# MC_Brekout-SPInew.net
KiCad netlist of a schematic drawn in EAGLE
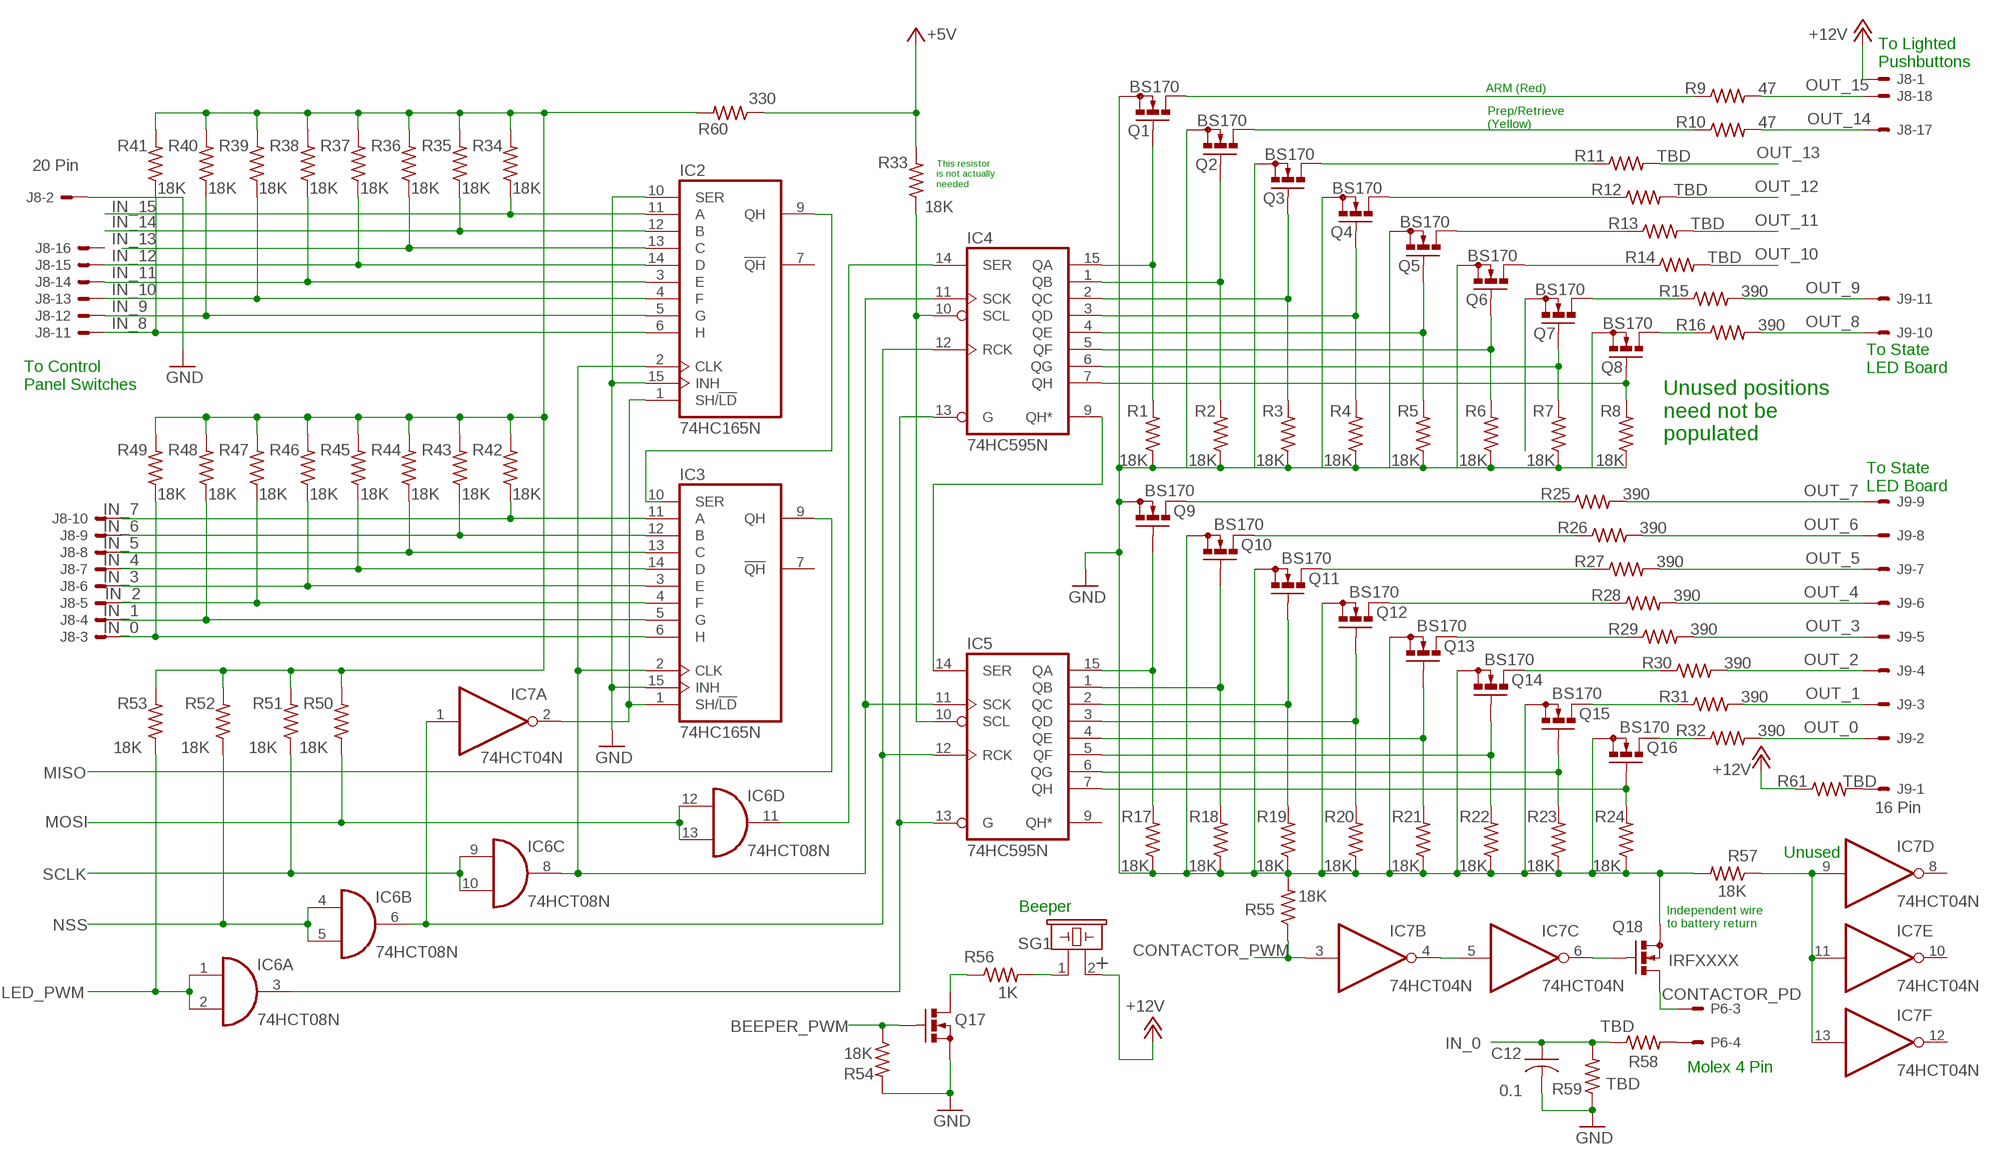
[diagram p0: schematic, sheet 1]

(export (version "E")
  (design (tool "Eeschema 10.0.6"))
  (components
    (comp (ref "C12")
      (value "0.1")
      (footprint "eagle-import:SMT0805")
      (libsource (lib "eagle-import") (part "SMT0805"))
    )
    (comp (ref "IC2")
      (value "74HC165N")
      (footprint "eagle-import:DIL16")
      (libsource (lib "eagle-import") (part "74165NHC"))
    )
    (comp (ref "IC3")
      (value "74HC165N")
      (footprint "eagle-import:DIL16")
      (libsource (lib "eagle-import") (part "74165NHC"))
    )
    (comp (ref "IC4")
      (value "74HC595N")
      (footprint "eagle-import:DIL16")
      (libsource (lib "eagle-import") (part "74595NHC"))
    )
    (comp (ref "IC5")
      (value "74HC595N")
      (footprint "eagle-import:DIL16")
      (libsource (lib "eagle-import") (part "74595NHC"))
    )
    (comp (ref "IC6")
      (value "74HCT08N")
      (footprint "eagle-import:DIL14")
      (libsource (lib "eagle-import") (part "7408NHCT"))
    )
    (comp (ref "IC7")
      (value "74HCT04N")
      (footprint "eagle-import:DIL14")
      (libsource (lib "eagle-import") (part "7404NHCT"))
    )
    (comp (ref "J8")
      (value "20 Pin")
      (footprint "eagle-import:70543-20")
      (libsource (lib "eagle-import") (part "C-GRID-20-70543"))
    )
    (comp (ref "J9")
      (value "16 Pin")
      (footprint "eagle-import:22-23-2121")
      (fields (field (name "MF") "MOLEX") (field (name "MPN") "22-23-2121"))
      (libsource (lib "eagle-import") (part "22-23-2121"))
    )
    (comp (ref "P6")
      (value "Molex 4 Pin")
      (footprint "eagle-import:22-23-2041")
      (fields (field (name "MF") "MOLEX") (field (name "MPN") "22-23-2041"))
      (libsource (lib "eagle-import") (part "22-23-2041"))
    )
    (comp (ref "Q1")
      (value "BS170")
      (footprint "eagle-import:SOT54E")
      (libsource (lib "eagle-import") (part "BS170"))
    )
    (comp (ref "Q2")
      (value "BS170")
      (footprint "eagle-import:SOT54E")
      (libsource (lib "eagle-import") (part "BS170"))
    )
    (comp (ref "Q3")
      (value "BS170")
      (footprint "eagle-import:SOT54E")
      (libsource (lib "eagle-import") (part "BS170"))
    )
    (comp (ref "Q4")
      (value "BS170")
      (footprint "eagle-import:SOT54E")
      (libsource (lib "eagle-import") (part "BS170"))
    )
    (comp (ref "Q5")
      (value "BS170")
      (footprint "eagle-import:SOT54E")
      (libsource (lib "eagle-import") (part "BS170"))
    )
    (comp (ref "Q6")
      (value "BS170")
      (footprint "eagle-import:SOT54E")
      (libsource (lib "eagle-import") (part "BS170"))
    )
    (comp (ref "Q7")
      (value "BS170")
      (footprint "eagle-import:SOT54E")
      (libsource (lib "eagle-import") (part "BS170"))
    )
    (comp (ref "Q8")
      (value "BS170")
      (footprint "eagle-import:SOT54E")
      (libsource (lib "eagle-import") (part "BS170"))
    )
    (comp (ref "Q9")
      (value "BS170")
      (footprint "eagle-import:SOT54E")
      (libsource (lib "eagle-import") (part "BS170"))
    )
    (comp (ref "Q10")
      (value "BS170")
      (footprint "eagle-import:SOT54E")
      (libsource (lib "eagle-import") (part "BS170"))
    )
    (comp (ref "Q11")
      (value "BS170")
      (footprint "eagle-import:SOT54E")
      (libsource (lib "eagle-import") (part "BS170"))
    )
    (comp (ref "Q12")
      (value "BS170")
      (footprint "eagle-import:SOT54E")
      (libsource (lib "eagle-import") (part "BS170"))
    )
    (comp (ref "Q13")
      (value "BS170")
      (footprint "eagle-import:SOT54E")
      (libsource (lib "eagle-import") (part "BS170"))
    )
    (comp (ref "Q14")
      (value "BS170")
      (footprint "eagle-import:SOT54E")
      (libsource (lib "eagle-import") (part "BS170"))
    )
    (comp (ref "Q15")
      (value "BS170")
      (footprint "eagle-import:SOT54E")
      (libsource (lib "eagle-import") (part "BS170"))
    )
    (comp (ref "Q16")
      (value "BS170")
      (footprint "eagle-import:SOT54E")
      (libsource (lib "eagle-import") (part "BS170"))
    )
    (comp (ref "Q17")
      (value "BS170")
      (footprint "eagle-import:SOT54E")
      (libsource (lib "eagle-import") (part "BS170"))
    )
    (comp (ref "Q18")
      (value "IRFXXXX")
      (footprint "eagle-import:SOT54E")
      (libsource (lib "eagle-import") (part "BS170"))
    )
    (comp (ref "R1")
      (value "18K")
      (footprint "eagle-import:V234_12")
      (libsource (lib "eagle-import") (part "R-US_V234/12"))
    )
    (comp (ref "R2")
      (value "18K")
      (footprint "eagle-import:V234_12")
      (libsource (lib "eagle-import") (part "R-US_V234/12"))
    )
    (comp (ref "R3")
      (value "18K")
      (footprint "eagle-import:V234_12")
      (libsource (lib "eagle-import") (part "R-US_V234/12"))
    )
    (comp (ref "R4")
      (value "18K")
      (footprint "eagle-import:V234_12")
      (libsource (lib "eagle-import") (part "R-US_V234/12"))
    )
    (comp (ref "R5")
      (value "18K")
      (footprint "eagle-import:V234_12")
      (libsource (lib "eagle-import") (part "R-US_V234/12"))
    )
    (comp (ref "R6")
      (value "18K")
      (footprint "eagle-import:V234_12")
      (libsource (lib "eagle-import") (part "R-US_V234/12"))
    )
    (comp (ref "R7")
      (value "18K")
      (footprint "eagle-import:V234_12")
      (libsource (lib "eagle-import") (part "R-US_V234/12"))
    )
    (comp (ref "R8")
      (value "18K")
      (footprint "eagle-import:V234_12")
      (libsource (lib "eagle-import") (part "R-US_V234/12"))
    )
    (comp (ref "R9")
      (value "47")
      (footprint "eagle-import:V234_12")
      (libsource (lib "eagle-import") (part "R-US_V234/12"))
    )
    (comp (ref "R10")
      (value "47")
      (footprint "eagle-import:V234_12")
      (libsource (lib "eagle-import") (part "R-US_V234/12"))
    )
    (comp (ref "R11")
      (value "TBD")
      (footprint "eagle-import:V234_12")
      (libsource (lib "eagle-import") (part "R-US_V234/12"))
    )
    (comp (ref "R12")
      (value "TBD")
      (footprint "eagle-import:V234_12")
      (libsource (lib "eagle-import") (part "R-US_V234/12"))
    )
    (comp (ref "R13")
      (value "TBD")
      (footprint "eagle-import:V234_12")
      (libsource (lib "eagle-import") (part "R-US_V234/12"))
    )
    (comp (ref "R14")
      (value "TBD")
      (footprint "eagle-import:V234_12")
      (libsource (lib "eagle-import") (part "R-US_V234/12"))
    )
    (comp (ref "R15")
      (value "390")
      (footprint "eagle-import:V234_12")
      (libsource (lib "eagle-import") (part "R-US_V234/12"))
    )
    (comp (ref "R16")
      (value "390")
      (footprint "eagle-import:V234_12")
      (libsource (lib "eagle-import") (part "R-US_V234/12"))
    )
    (comp (ref "R17")
      (value "18K")
      (footprint "eagle-import:V234_12")
      (libsource (lib "eagle-import") (part "R-US_V234/12"))
    )
    (comp (ref "R18")
      (value "18K")
      (footprint "eagle-import:V234_12")
      (libsource (lib "eagle-import") (part "R-US_V234/12"))
    )
    (comp (ref "R19")
      (value "18K")
      (footprint "eagle-import:V234_12")
      (libsource (lib "eagle-import") (part "R-US_V234/12"))
    )
    (comp (ref "R20")
      (value "18K")
      (footprint "eagle-import:V234_12")
      (libsource (lib "eagle-import") (part "R-US_V234/12"))
    )
    (comp (ref "R21")
      (value "18K")
      (footprint "eagle-import:V234_12")
      (libsource (lib "eagle-import") (part "R-US_V234/12"))
    )
    (comp (ref "R22")
      (value "18K")
      (footprint "eagle-import:V234_12")
      (libsource (lib "eagle-import") (part "R-US_V234/12"))
    )
    (comp (ref "R23")
      (value "18K")
      (footprint "eagle-import:V234_12")
      (libsource (lib "eagle-import") (part "R-US_V234/12"))
    )
    (comp (ref "R24")
      (value "18K")
      (footprint "eagle-import:V234_12")
      (libsource (lib "eagle-import") (part "R-US_V234/12"))
    )
    (comp (ref "R25")
      (value "390")
      (footprint "eagle-import:V234_12")
      (libsource (lib "eagle-import") (part "R-US_V234/12"))
    )
    (comp (ref "R26")
      (value "390")
      (footprint "eagle-import:V234_12")
      (libsource (lib "eagle-import") (part "R-US_V234/12"))
    )
    (comp (ref "R27")
      (value "390")
      (footprint "eagle-import:V234_12")
      (libsource (lib "eagle-import") (part "R-US_V234/12"))
    )
    (comp (ref "R28")
      (value "390")
      (footprint "eagle-import:V234_12")
      (libsource (lib "eagle-import") (part "R-US_V234/12"))
    )
    (comp (ref "R29")
      (value "390")
      (footprint "eagle-import:V234_12")
      (libsource (lib "eagle-import") (part "R-US_V234/12"))
    )
    (comp (ref "R30")
      (value "390")
      (footprint "eagle-import:V234_12")
      (libsource (lib "eagle-import") (part "R-US_V234/12"))
    )
    (comp (ref "R31")
      (value "390")
      (footprint "eagle-import:V234_12")
      (libsource (lib "eagle-import") (part "R-US_V234/12"))
    )
    (comp (ref "R32")
      (value "390")
      (footprint "eagle-import:V234_12")
      (libsource (lib "eagle-import") (part "R-US_V234/12"))
    )
    (comp (ref "R33")
      (value "18K")
      (footprint "eagle-import:V234_12")
      (libsource (lib "eagle-import") (part "R-US_V234/12"))
    )
    (comp (ref "R34")
      (value "18K")
      (footprint "eagle-import:V234_12")
      (libsource (lib "eagle-import") (part "R-US_V234/12"))
    )
    (comp (ref "R35")
      (value "18K")
      (footprint "eagle-import:V234_12")
      (libsource (lib "eagle-import") (part "R-US_V234/12"))
    )
    (comp (ref "R36")
      (value "18K")
      (footprint "eagle-import:V234_12")
      (libsource (lib "eagle-import") (part "R-US_V234/12"))
    )
    (comp (ref "R37")
      (value "18K")
      (footprint "eagle-import:V234_12")
      (libsource (lib "eagle-import") (part "R-US_V234/12"))
    )
    (comp (ref "R38")
      (value "18K")
      (footprint "eagle-import:V234_12")
      (libsource (lib "eagle-import") (part "R-US_V234/12"))
    )
    (comp (ref "R39")
      (value "18K")
      (footprint "eagle-import:V234_12")
      (libsource (lib "eagle-import") (part "R-US_V234/12"))
    )
    (comp (ref "R40")
      (value "18K")
      (footprint "eagle-import:V234_12")
      (libsource (lib "eagle-import") (part "R-US_V234/12"))
    )
    (comp (ref "R41")
      (value "18K")
      (footprint "eagle-import:V234_12")
      (libsource (lib "eagle-import") (part "R-US_V234/12"))
    )
    (comp (ref "R42")
      (value "18K")
      (footprint "eagle-import:V234_12")
      (libsource (lib "eagle-import") (part "R-US_V234/12"))
    )
    (comp (ref "R43")
      (value "18K")
      (footprint "eagle-import:V234_12")
      (libsource (lib "eagle-import") (part "R-US_V234/12"))
    )
    (comp (ref "R44")
      (value "18K")
      (footprint "eagle-import:V234_12")
      (libsource (lib "eagle-import") (part "R-US_V234/12"))
    )
    (comp (ref "R45")
      (value "18K")
      (footprint "eagle-import:V234_12")
      (libsource (lib "eagle-import") (part "R-US_V234/12"))
    )
    (comp (ref "R46")
      (value "18K")
      (footprint "eagle-import:V234_12")
      (libsource (lib "eagle-import") (part "R-US_V234/12"))
    )
    (comp (ref "R47")
      (value "18K")
      (footprint "eagle-import:V234_12")
      (libsource (lib "eagle-import") (part "R-US_V234/12"))
    )
    (comp (ref "R48")
      (value "18K")
      (footprint "eagle-import:V234_12")
      (libsource (lib "eagle-import") (part "R-US_V234/12"))
    )
    (comp (ref "R49")
      (value "18K")
      (footprint "eagle-import:V234_12")
      (libsource (lib "eagle-import") (part "R-US_V234/12"))
    )
    (comp (ref "R50")
      (value "18K")
      (footprint "eagle-import:V234_12")
      (libsource (lib "eagle-import") (part "R-US_V234/12"))
    )
    (comp (ref "R51")
      (value "18K")
      (footprint "eagle-import:V234_12")
      (libsource (lib "eagle-import") (part "R-US_V234/12"))
    )
    (comp (ref "R52")
      (value "18K")
      (footprint "eagle-import:V234_12")
      (libsource (lib "eagle-import") (part "R-US_V234/12"))
    )
    (comp (ref "R53")
      (value "18K")
      (footprint "eagle-import:V234_12")
      (libsource (lib "eagle-import") (part "R-US_V234/12"))
    )
    (comp (ref "R54")
      (value "18K")
      (footprint "eagle-import:V234_12")
      (libsource (lib "eagle-import") (part "R-US_V234/12"))
    )
    (comp (ref "R55")
      (value "18K")
      (footprint "eagle-import:V234_12")
      (libsource (lib "eagle-import") (part "R-US_V234/12"))
    )
    (comp (ref "R56")
      (value "1K")
      (footprint "eagle-import:V234_12")
      (libsource (lib "eagle-import") (part "R-US_V234/12"))
    )
    (comp (ref "R57")
      (value "18K")
      (footprint "eagle-import:V234_12")
      (libsource (lib "eagle-import") (part "R-US_V234/12"))
    )
    (comp (ref "R58")
      (value "TBD")
      (footprint "eagle-import:V234_12")
      (libsource (lib "eagle-import") (part "R-US_V234/12"))
    )
    (comp (ref "R59")
      (value "TBD")
      (footprint "eagle-import:V234_12")
      (libsource (lib "eagle-import") (part "R-US_V234/12"))
    )
    (comp (ref "R60")
      (value "330")
      (footprint "eagle-import:V234_12")
      (libsource (lib "eagle-import") (part "R-US_V234/12"))
    )
    (comp (ref "R61")
      (value "TBD")
      (footprint "eagle-import:V234_12")
      (libsource (lib "eagle-import") (part "R-US_V234/12"))
    )
    (comp (ref "SG1")
      (value "EFBAA40D101")
      (footprint "eagle-import:EFBAA40D101")
      (libsource (lib "eagle-import") (part "EFB?AA40D101"))
    )
  )
  (nets
    (net (code "1") (name "+5V") (class "Default")
      (node (ref "R33") (pin "2") (pinfunction "2_2") (pintype "passive"))
      (node (ref "R60") (pin "1") (pinfunction "1_1") (pintype "passive"))
    )
    (net (code "2") (name "+12V") (class "Default")
      (node (ref "J8") (pin "1") (pinfunction "S_1") (pintype "passive"))
      (node (ref "R61") (pin "1") (pinfunction "1_1") (pintype "passive"))
      (node (ref "SG1") (pin "2") (pinfunction "2_2") (pintype "passive"))
    )
    (net (code "3") (name "/BEEPER_PWM") (class "Default")
      (node (ref "Q17") (pin "G") (pinfunction "G_G") (pintype "passive"))
      (node (ref "R54") (pin "1") (pinfunction "1_1") (pintype "passive"))
    )
    (net (code "4") (name "/CONTACTOR_PD") (class "Default")
      (node (ref "P6") (pin "3") (pinfunction "S_3") (pintype "passive"))
      (node (ref "Q18") (pin "D") (pinfunction "D_D") (pintype "passive"))
    )
    (net (code "5") (name "/CONTACTOR_PWM") (class "Default")
      (node (ref "IC7") (pin "3") (pinfunction "I_3") (pintype "input"))
      (node (ref "R55") (pin "1") (pinfunction "1_1") (pintype "passive"))
    )
    (net (code "6") (name "/IN_0") (class "Default")
      (node (ref "C12") (pin "P$1") (pinfunction "1_P$1") (pintype "passive"))
      (node (ref "IC3") (pin "6") (pinfunction "H_6") (pintype "input"))
      (node (ref "J8") (pin "3") (pinfunction "S_3") (pintype "passive"))
      (node (ref "R49") (pin "1") (pinfunction "1_1") (pintype "passive"))
      (node (ref "R58") (pin "1") (pinfunction "1_1") (pintype "passive"))
      (node (ref "R59") (pin "2") (pinfunction "2_2") (pintype "passive"))
    )
    (net (code "7") (name "/IN_1") (class "Default")
      (node (ref "IC3") (pin "5") (pinfunction "G_5") (pintype "input"))
      (node (ref "J8") (pin "4") (pinfunction "S_4") (pintype "passive"))
      (node (ref "R48") (pin "1") (pinfunction "1_1") (pintype "passive"))
    )
    (net (code "8") (name "/IN_2") (class "Default")
      (node (ref "IC3") (pin "4") (pinfunction "F_4") (pintype "input"))
      (node (ref "J8") (pin "5") (pinfunction "S_5") (pintype "passive"))
      (node (ref "R47") (pin "1") (pinfunction "1_1") (pintype "passive"))
    )
    (net (code "9") (name "/IN_3") (class "Default")
      (node (ref "IC3") (pin "3") (pinfunction "E_3") (pintype "input"))
      (node (ref "J8") (pin "6") (pinfunction "S_6") (pintype "passive"))
      (node (ref "R46") (pin "1") (pinfunction "1_1") (pintype "passive"))
    )
    (net (code "10") (name "/IN_4") (class "Default")
      (node (ref "IC3") (pin "14") (pinfunction "D_14") (pintype "input"))
      (node (ref "J8") (pin "7") (pinfunction "S_7") (pintype "passive"))
      (node (ref "R45") (pin "1") (pinfunction "1_1") (pintype "passive"))
    )
    (net (code "11") (name "/IN_5") (class "Default")
      (node (ref "IC3") (pin "13") (pinfunction "C_13") (pintype "input"))
      (node (ref "J8") (pin "8") (pinfunction "S_8") (pintype "passive"))
      (node (ref "R44") (pin "1") (pinfunction "1_1") (pintype "passive"))
    )
    (net (code "12") (name "/IN_6") (class "Default")
      (node (ref "IC3") (pin "12") (pinfunction "B_12") (pintype "input"))
      (node (ref "J8") (pin "9") (pinfunction "S_9") (pintype "passive"))
      (node (ref "R43") (pin "1") (pinfunction "1_1") (pintype "passive"))
    )
    (net (code "13") (name "/IN_7") (class "Default")
      (node (ref "IC3") (pin "11") (pinfunction "A_11") (pintype "input"))
      (node (ref "J8") (pin "10") (pinfunction "S_10") (pintype "passive"))
      (node (ref "R42") (pin "1") (pinfunction "1_1") (pintype "passive"))
    )
    (net (code "14") (name "/IN_8") (class "Default")
      (node (ref "IC2") (pin "6") (pinfunction "H_6") (pintype "input"))
      (node (ref "J8") (pin "11") (pinfunction "S_11") (pintype "passive"))
      (node (ref "R41") (pin "1") (pinfunction "1_1") (pintype "passive"))
    )
    (net (code "15") (name "/IN_9") (class "Default")
      (node (ref "IC2") (pin "5") (pinfunction "G_5") (pintype "input"))
      (node (ref "J8") (pin "12") (pinfunction "S_12") (pintype "passive"))
      (node (ref "R40") (pin "1") (pinfunction "1_1") (pintype "passive"))
    )
    (net (code "16") (name "/IN_10") (class "Default")
      (node (ref "IC2") (pin "4") (pinfunction "F_4") (pintype "input"))
      (node (ref "J8") (pin "13") (pinfunction "S_13") (pintype "passive"))
      (node (ref "R39") (pin "1") (pinfunction "1_1") (pintype "passive"))
    )
    (net (code "17") (name "/IN_11") (class "Default")
      (node (ref "IC2") (pin "3") (pinfunction "E_3") (pintype "input"))
      (node (ref "J8") (pin "14") (pinfunction "S_14") (pintype "passive"))
      (node (ref "R38") (pin "1") (pinfunction "1_1") (pintype "passive"))
    )
    (net (code "18") (name "/IN_12") (class "Default")
      (node (ref "IC2") (pin "14") (pinfunction "D_14") (pintype "input"))
      (node (ref "J8") (pin "15") (pinfunction "S_15") (pintype "passive"))
      (node (ref "R37") (pin "1") (pinfunction "1_1") (pintype "passive"))
    )
    (net (code "19") (name "/IN_13") (class "Default")
      (node (ref "IC2") (pin "13") (pinfunction "C_13") (pintype "input"))
      (node (ref "R36") (pin "1") (pinfunction "1_1") (pintype "passive"))
    )
    (net (code "20") (name "/IN_14") (class "Default")
      (node (ref "IC2") (pin "12") (pinfunction "B_12") (pintype "input"))
      (node (ref "R35") (pin "1") (pinfunction "1_1") (pintype "passive"))
    )
    (net (code "21") (name "/IN_15") (class "Default")
      (node (ref "IC2") (pin "11") (pinfunction "A_11") (pintype "input"))
      (node (ref "R34") (pin "1") (pinfunction "1_1") (pintype "passive"))
    )
    (net (code "22") (name "/LED_PWM") (class "Default")
      (node (ref "IC6") (pin "1") (pinfunction "I0_1") (pintype "input"))
      (node (ref "IC6") (pin "2") (pinfunction "I1_2") (pintype "input"))
      (node (ref "R53") (pin "1") (pinfunction "1_1") (pintype "passive"))
    )
    (net (code "23") (name "/MISO") (class "Default")
      (node (ref "IC3") (pin "9") (pinfunction "QH_9") (pintype "output"))
    )
    (net (code "24") (name "/MOSI") (class "Default")
      (node (ref "IC6") (pin "12") (pinfunction "I0_12") (pintype "input"))
      (node (ref "IC6") (pin "13") (pinfunction "I1_13") (pintype "input"))
      (node (ref "R50") (pin "1") (pinfunction "1_1") (pintype "passive"))
    )
    (net (code "25") (name "/NSS") (class "Default")
      (node (ref "IC6") (pin "4") (pinfunction "I0_4") (pintype "input"))
      (node (ref "IC6") (pin "5") (pinfunction "I1_5") (pintype "input"))
      (node (ref "R52") (pin "1") (pinfunction "1_1") (pintype "passive"))
    )
    (net (code "26") (name "/OUT_0") (class "Default")
      (node (ref "J9") (pin "2") (pinfunction "S_2") (pintype "passive"))
      (node (ref "R32") (pin "2") (pinfunction "2_2") (pintype "passive"))
    )
    (net (code "27") (name "/OUT_1") (class "Default")
      (node (ref "J9") (pin "3") (pinfunction "S_3") (pintype "passive"))
      (node (ref "R31") (pin "2") (pinfunction "2_2") (pintype "passive"))
    )
    (net (code "28") (name "/OUT_2") (class "Default")
      (node (ref "J9") (pin "4") (pinfunction "S_4") (pintype "passive"))
      (node (ref "R30") (pin "2") (pinfunction "2_2") (pintype "passive"))
    )
    (net (code "29") (name "/OUT_3") (class "Default")
      (node (ref "J9") (pin "5") (pinfunction "S_5") (pintype "passive"))
      (node (ref "R29") (pin "2") (pinfunction "2_2") (pintype "passive"))
    )
    (net (code "30") (name "/OUT_4") (class "Default")
      (node (ref "J9") (pin "6") (pinfunction "S_6") (pintype "passive"))
      (node (ref "R28") (pin "2") (pinfunction "2_2") (pintype "passive"))
    )
    (net (code "31") (name "/OUT_5") (class "Default")
      (node (ref "J9") (pin "7") (pinfunction "S_7") (pintype "passive"))
      (node (ref "R27") (pin "2") (pinfunction "2_2") (pintype "passive"))
    )
    (net (code "32") (name "/OUT_6") (class "Default")
      (node (ref "J9") (pin "8") (pinfunction "S_8") (pintype "passive"))
      (node (ref "R26") (pin "2") (pinfunction "2_2") (pintype "passive"))
    )
    (net (code "33") (name "/OUT_7") (class "Default")
      (node (ref "J9") (pin "9") (pinfunction "S_9") (pintype "passive"))
      (node (ref "R25") (pin "2") (pinfunction "2_2") (pintype "passive"))
    )
    (net (code "34") (name "/OUT_8") (class "Default")
      (node (ref "J9") (pin "10") (pinfunction "S_10") (pintype "passive"))
      (node (ref "R16") (pin "2") (pinfunction "2_2") (pintype "passive"))
    )
    (net (code "35") (name "/OUT_9") (class "Default")
      (node (ref "J9") (pin "11") (pinfunction "S_11") (pintype "passive"))
      (node (ref "R15") (pin "2") (pinfunction "2_2") (pintype "passive"))
    )
    (net (code "36") (name "/OUT_10") (class "Default")
      (node (ref "R14") (pin "2") (pinfunction "2_2") (pintype "passive"))
    )
    (net (code "37") (name "/OUT_11") (class "Default")
      (node (ref "R13") (pin "2") (pinfunction "2_2") (pintype "passive"))
    )
    (net (code "38") (name "/OUT_12") (class "Default")
      (node (ref "R12") (pin "2") (pinfunction "2_2") (pintype "passive"))
    )
    (net (code "39") (name "/OUT_13") (class "Default")
      (node (ref "R11") (pin "2") (pinfunction "2_2") (pintype "passive"))
    )
    (net (code "40") (name "/OUT_14") (class "Default")
      (node (ref "J8") (pin "17") (pinfunction "S_17") (pintype "passive"))
      (node (ref "R10") (pin "2") (pinfunction "2_2") (pintype "passive"))
    )
    (net (code "41") (name "/OUT_15") (class "Default")
      (node (ref "J8") (pin "18") (pinfunction "S_18") (pintype "passive"))
      (node (ref "R9") (pin "2") (pinfunction "2_2") (pintype "passive"))
    )
    (net (code "42") (name "/SCLK") (class "Default")
      (node (ref "IC6") (pin "10") (pinfunction "I1_10") (pintype "input"))
      (node (ref "IC6") (pin "9") (pinfunction "I0_9") (pintype "input"))
      (node (ref "R51") (pin "1") (pinfunction "1_1") (pintype "passive"))
    )
    (net (code "43") (name "GND") (class "Default")
      (node (ref "C12") (pin "P$2") (pinfunction "2_P$2") (pintype "passive"))
      (node (ref "IC2") (pin "10") (pinfunction "SER_10") (pintype "input"))
      (node (ref "IC2") (pin "15") (pinfunction "INH_15") (pintype "input"))
      (node (ref "IC3") (pin "15") (pinfunction "INH_15") (pintype "input"))
      (node (ref "J8") (pin "2") (pinfunction "S_2") (pintype "passive"))
      (node (ref "Q1") (pin "S") (pinfunction "S_S") (pintype "passive"))
      (node (ref "Q10") (pin "S") (pinfunction "S_S") (pintype "passive"))
      (node (ref "Q11") (pin "S") (pinfunction "S_S") (pintype "passive"))
      (node (ref "Q12") (pin "S") (pinfunction "S_S") (pintype "passive"))
      (node (ref "Q13") (pin "S") (pinfunction "S_S") (pintype "passive"))
      (node (ref "Q14") (pin "S") (pinfunction "S_S") (pintype "passive"))
      (node (ref "Q15") (pin "S") (pinfunction "S_S") (pintype "passive"))
      (node (ref "Q16") (pin "S") (pinfunction "S_S") (pintype "passive"))
      (node (ref "Q17") (pin "S") (pinfunction "S_S") (pintype "passive"))
      (node (ref "Q18") (pin "S") (pinfunction "S_S") (pintype "passive"))
      (node (ref "Q9") (pin "S") (pinfunction "S_S") (pintype "passive"))
      (node (ref "R1") (pin "1") (pinfunction "1_1") (pintype "passive"))
      (node (ref "R17") (pin "1") (pinfunction "1_1") (pintype "passive"))
      (node (ref "R18") (pin "1") (pinfunction "1_1") (pintype "passive"))
      (node (ref "R19") (pin "1") (pinfunction "1_1") (pintype "passive"))
      (node (ref "R2") (pin "1") (pinfunction "1_1") (pintype "passive"))
      (node (ref "R20") (pin "1") (pinfunction "1_1") (pintype "passive"))
      (node (ref "R21") (pin "1") (pinfunction "1_1") (pintype "passive"))
      (node (ref "R22") (pin "1") (pinfunction "1_1") (pintype "passive"))
      (node (ref "R23") (pin "1") (pinfunction "1_1") (pintype "passive"))
      (node (ref "R24") (pin "1") (pinfunction "1_1") (pintype "passive"))
      (node (ref "R3") (pin "1") (pinfunction "1_1") (pintype "passive"))
      (node (ref "R4") (pin "1") (pinfunction "1_1") (pintype "passive"))
      (node (ref "R5") (pin "1") (pinfunction "1_1") (pintype "passive"))
      (node (ref "R54") (pin "2") (pinfunction "2_2") (pintype "passive"))
      (node (ref "R55") (pin "2") (pinfunction "2_2") (pintype "passive"))
      (node (ref "R57") (pin "2") (pinfunction "2_2") (pintype "passive"))
      (node (ref "R59") (pin "1") (pinfunction "1_1") (pintype "passive"))
      (node (ref "R6") (pin "1") (pinfunction "1_1") (pintype "passive"))
      (node (ref "R7") (pin "1") (pinfunction "1_1") (pintype "passive"))
      (node (ref "R8") (pin "1") (pinfunction "1_1") (pintype "passive"))
    )
    (net (code "44") (name "Net-(IC2A-CLK)") (class "Default")
      (node (ref "IC2") (pin "2") (pinfunction "CLK_2") (pintype "input"))
      (node (ref "IC3") (pin "2") (pinfunction "CLK_2") (pintype "input"))
      (node (ref "IC4") (pin "11") (pinfunction "SCK_11") (pintype "input"))
      (node (ref "IC5") (pin "11") (pinfunction "SCK_11") (pintype "input"))
      (node (ref "IC6") (pin "8") (pinfunction "O_8") (pintype "output"))
    )
    (net (code "45") (name "Net-(IC2A-QH)") (class "Default")
      (node (ref "IC2") (pin "9") (pinfunction "QH_9") (pintype "output"))
      (node (ref "IC3") (pin "10") (pinfunction "SER_10") (pintype "input"))
    )
    (net (code "46") (name "Net-(IC2A-SH{slash}~{LD})") (class "Default")
      (node (ref "IC2") (pin "1") (pinfunction "SH/~{LD}_1") (pintype "input"))
      (node (ref "IC3") (pin "1") (pinfunction "SH/~{LD}_1") (pintype "input"))
      (node (ref "IC7") (pin "2") (pinfunction "O_2") (pintype "output"))
    )
    (net (code "47") (name "Net-(IC4A-G)") (class "Default")
      (node (ref "IC4") (pin "13") (pinfunction "G_13") (pintype "input"))
      (node (ref "IC5") (pin "13") (pinfunction "G_13") (pintype "input"))
      (node (ref "IC6") (pin "3") (pinfunction "O_3") (pintype "output"))
    )
    (net (code "48") (name "Net-(IC4A-QA)") (class "Default")
      (node (ref "IC4") (pin "15") (pinfunction "QA_15") (pintype "tri_state"))
      (node (ref "Q1") (pin "G") (pinfunction "G_G") (pintype "passive"))
      (node (ref "R1") (pin "2") (pinfunction "2_2") (pintype "passive"))
    )
    (net (code "49") (name "Net-(IC4A-QB)") (class "Default")
      (node (ref "IC4") (pin "1") (pinfunction "QB_1") (pintype "tri_state"))
      (node (ref "Q2") (pin "G") (pinfunction "G_G") (pintype "passive"))
      (node (ref "R2") (pin "2") (pinfunction "2_2") (pintype "passive"))
    )
    (net (code "50") (name "Net-(IC4A-QC)") (class "Default")
      (node (ref "IC4") (pin "2") (pinfunction "QC_2") (pintype "tri_state"))
      (node (ref "Q3") (pin "G") (pinfunction "G_G") (pintype "passive"))
      (node (ref "R3") (pin "2") (pinfunction "2_2") (pintype "passive"))
    )
    (net (code "51") (name "Net-(IC4A-QD)") (class "Default")
      (node (ref "IC4") (pin "3") (pinfunction "QD_3") (pintype "tri_state"))
      (node (ref "Q4") (pin "G") (pinfunction "G_G") (pintype "passive"))
      (node (ref "R4") (pin "2") (pinfunction "2_2") (pintype "passive"))
    )
    (net (code "52") (name "Net-(IC4A-QE)") (class "Default")
      (node (ref "IC4") (pin "4") (pinfunction "QE_4") (pintype "tri_state"))
      (node (ref "Q5") (pin "G") (pinfunction "G_G") (pintype "passive"))
      (node (ref "R5") (pin "2") (pinfunction "2_2") (pintype "passive"))
    )
    (net (code "53") (name "Net-(IC4A-QF)") (class "Default")
      (node (ref "IC4") (pin "5") (pinfunction "QF_5") (pintype "tri_state"))
      (node (ref "Q6") (pin "G") (pinfunction "G_G") (pintype "passive"))
      (node (ref "R6") (pin "2") (pinfunction "2_2") (pintype "passive"))
    )
    (net (code "54") (name "Net-(IC4A-QG)") (class "Default")
      (node (ref "IC4") (pin "6") (pinfunction "QG_6") (pintype "tri_state"))
      (node (ref "Q7") (pin "G") (pinfunction "G_G") (pintype "passive"))
      (node (ref "R7") (pin "2") (pinfunction "2_2") (pintype "passive"))
    )
    (net (code "55") (name "Net-(IC4A-QH)") (class "Default")
      (node (ref "IC4") (pin "7") (pinfunction "QH_7") (pintype "tri_state"))
      (node (ref "Q8") (pin "G") (pinfunction "G_G") (pintype "passive"))
      (node (ref "R8") (pin "2") (pinfunction "2_2") (pintype "passive"))
    )
    (net (code "56") (name "Net-(IC4A-QH*)") (class "Default")
      (node (ref "IC4") (pin "9") (pinfunction "QH*_9") (pintype "tri_state"))
      (node (ref "IC5") (pin "14") (pinfunction "SER_14") (pintype "input"))
    )
    (net (code "57") (name "Net-(IC4A-RCK)") (class "Default")
      (node (ref "IC4") (pin "12") (pinfunction "RCK_12") (pintype "input"))
      (node (ref "IC5") (pin "12") (pinfunction "RCK_12") (pintype "input"))
      (node (ref "IC6") (pin "6") (pinfunction "O_6") (pintype "output"))
      (node (ref "IC7") (pin "1") (pinfunction "I_1") (pintype "input"))
    )
    (net (code "58") (name "Net-(IC4A-SCL)") (class "Default")
      (node (ref "IC4") (pin "10") (pinfunction "SCL_10") (pintype "input"))
      (node (ref "IC5") (pin "10") (pinfunction "SCL_10") (pintype "input"))
      (node (ref "R33") (pin "1") (pinfunction "1_1") (pintype "passive"))
    )
    (net (code "59") (name "Net-(IC4A-SER)") (class "Default")
      (node (ref "IC4") (pin "14") (pinfunction "SER_14") (pintype "input"))
      (node (ref "IC6") (pin "11") (pinfunction "O_11") (pintype "output"))
    )
    (net (code "60") (name "Net-(IC5A-QA)") (class "Default")
      (node (ref "IC5") (pin "15") (pinfunction "QA_15") (pintype "tri_state"))
      (node (ref "Q9") (pin "G") (pinfunction "G_G") (pintype "passive"))
      (node (ref "R17") (pin "2") (pinfunction "2_2") (pintype "passive"))
    )
    (net (code "61") (name "Net-(IC5A-QB)") (class "Default")
      (node (ref "IC5") (pin "1") (pinfunction "QB_1") (pintype "tri_state"))
      (node (ref "Q10") (pin "G") (pinfunction "G_G") (pintype "passive"))
      (node (ref "R18") (pin "2") (pinfunction "2_2") (pintype "passive"))
    )
    (net (code "62") (name "Net-(IC5A-QC)") (class "Default")
      (node (ref "IC5") (pin "2") (pinfunction "QC_2") (pintype "tri_state"))
      (node (ref "Q11") (pin "G") (pinfunction "G_G") (pintype "passive"))
      (node (ref "R19") (pin "2") (pinfunction "2_2") (pintype "passive"))
    )
    (net (code "63") (name "Net-(IC5A-QD)") (class "Default")
      (node (ref "IC5") (pin "3") (pinfunction "QD_3") (pintype "tri_state"))
      (node (ref "Q12") (pin "G") (pinfunction "G_G") (pintype "passive"))
      (node (ref "R20") (pin "2") (pinfunction "2_2") (pintype "passive"))
    )
    (net (code "64") (name "Net-(IC5A-QE)") (class "Default")
      (node (ref "IC5") (pin "4") (pinfunction "QE_4") (pintype "tri_state"))
      (node (ref "Q13") (pin "G") (pinfunction "G_G") (pintype "passive"))
      (node (ref "R21") (pin "2") (pinfunction "2_2") (pintype "passive"))
    )
    (net (code "65") (name "Net-(IC5A-QF)") (class "Default")
      (node (ref "IC5") (pin "5") (pinfunction "QF_5") (pintype "tri_state"))
      (node (ref "Q14") (pin "G") (pinfunction "G_G") (pintype "passive"))
      (node (ref "R22") (pin "2") (pinfunction "2_2") (pintype "passive"))
    )
    (net (code "66") (name "Net-(IC5A-QG)") (class "Default")
      (node (ref "IC5") (pin "6") (pinfunction "QG_6") (pintype "tri_state"))
      (node (ref "Q15") (pin "G") (pinfunction "G_G") (pintype "passive"))
      (node (ref "R23") (pin "2") (pinfunction "2_2") (pintype "passive"))
    )
    (net (code "67") (name "Net-(IC5A-QH)") (class "Default")
      (node (ref "IC5") (pin "7") (pinfunction "QH_7") (pintype "tri_state"))
      (node (ref "Q16") (pin "G") (pinfunction "G_G") (pintype "passive"))
      (node (ref "R24") (pin "2") (pinfunction "2_2") (pintype "passive"))
    )
    (net (code "68") (name "Net-(IC7B-O)") (class "Default")
      (node (ref "IC7") (pin "4") (pinfunction "O_4") (pintype "output"))
      (node (ref "IC7") (pin "5") (pinfunction "I_5") (pintype "input"))
    )
    (net (code "69") (name "Net-(IC7C-O)") (class "Default")
      (node (ref "IC7") (pin "6") (pinfunction "O_6") (pintype "output"))
      (node (ref "Q18") (pin "G") (pinfunction "G_G") (pintype "passive"))
    )
    (net (code "70") (name "Net-(IC7D-I)") (class "Default")
      (node (ref "IC7") (pin "11") (pinfunction "I_11") (pintype "input"))
      (node (ref "IC7") (pin "13") (pinfunction "I_13") (pintype "input"))
      (node (ref "IC7") (pin "9") (pinfunction "I_9") (pintype "input"))
      (node (ref "R57") (pin "1") (pinfunction "1_1") (pintype "passive"))
    )
    (net (code "71") (name "Net-(J9A-S)") (class "Default")
      (node (ref "J9") (pin "1") (pinfunction "S_1") (pintype "passive"))
      (node (ref "R61") (pin "2") (pinfunction "2_2") (pintype "passive"))
    )
    (net (code "72") (name "Net-(P6D-S)") (class "Default")
      (node (ref "P6") (pin "4") (pinfunction "S_4") (pintype "passive"))
      (node (ref "R58") (pin "2") (pinfunction "2_2") (pintype "passive"))
    )
    (net (code "73") (name "Net-(Q1-PadD)") (class "Default")
      (node (ref "Q1") (pin "D") (pinfunction "D_D") (pintype "passive"))
      (node (ref "R9") (pin "1") (pinfunction "1_1") (pintype "passive"))
    )
    (net (code "74") (name "Net-(Q2-PadD)") (class "Default")
      (node (ref "Q2") (pin "D") (pinfunction "D_D") (pintype "passive"))
      (node (ref "R10") (pin "1") (pinfunction "1_1") (pintype "passive"))
    )
    (net (code "75") (name "Net-(Q3-PadD)") (class "Default")
      (node (ref "Q3") (pin "D") (pinfunction "D_D") (pintype "passive"))
      (node (ref "R11") (pin "1") (pinfunction "1_1") (pintype "passive"))
    )
    (net (code "76") (name "Net-(Q4-PadD)") (class "Default")
      (node (ref "Q4") (pin "D") (pinfunction "D_D") (pintype "passive"))
      (node (ref "R12") (pin "1") (pinfunction "1_1") (pintype "passive"))
    )
    (net (code "77") (name "Net-(Q5-PadD)") (class "Default")
      (node (ref "Q5") (pin "D") (pinfunction "D_D") (pintype "passive"))
      (node (ref "R13") (pin "1") (pinfunction "1_1") (pintype "passive"))
    )
    (net (code "78") (name "Net-(Q6-PadD)") (class "Default")
      (node (ref "Q6") (pin "D") (pinfunction "D_D") (pintype "passive"))
      (node (ref "R14") (pin "1") (pinfunction "1_1") (pintype "passive"))
    )
    (net (code "79") (name "Net-(Q7-PadD)") (class "Default")
      (node (ref "Q7") (pin "D") (pinfunction "D_D") (pintype "passive"))
      (node (ref "R15") (pin "1") (pinfunction "1_1") (pintype "passive"))
    )
    (net (code "80") (name "Net-(Q8-PadD)") (class "Default")
      (node (ref "Q8") (pin "D") (pinfunction "D_D") (pintype "passive"))
      (node (ref "R16") (pin "1") (pinfunction "1_1") (pintype "passive"))
    )
    (net (code "81") (name "Net-(Q9-PadD)") (class "Default")
      (node (ref "Q9") (pin "D") (pinfunction "D_D") (pintype "passive"))
      (node (ref "R25") (pin "1") (pinfunction "1_1") (pintype "passive"))
    )
    (net (code "82") (name "Net-(Q10-PadD)") (class "Default")
      (node (ref "Q10") (pin "D") (pinfunction "D_D") (pintype "passive"))
      (node (ref "R26") (pin "1") (pinfunction "1_1") (pintype "passive"))
    )
    (net (code "83") (name "Net-(Q11-PadD)") (class "Default")
      (node (ref "Q11") (pin "D") (pinfunction "D_D") (pintype "passive"))
      (node (ref "R27") (pin "1") (pinfunction "1_1") (pintype "passive"))
    )
    (net (code "84") (name "Net-(Q12-PadD)") (class "Default")
      (node (ref "Q12") (pin "D") (pinfunction "D_D") (pintype "passive"))
      (node (ref "R28") (pin "1") (pinfunction "1_1") (pintype "passive"))
    )
    (net (code "85") (name "Net-(Q13-PadD)") (class "Default")
      (node (ref "Q13") (pin "D") (pinfunction "D_D") (pintype "passive"))
      (node (ref "R29") (pin "1") (pinfunction "1_1") (pintype "passive"))
    )
    (net (code "86") (name "Net-(Q14-PadD)") (class "Default")
      (node (ref "Q14") (pin "D") (pinfunction "D_D") (pintype "passive"))
      (node (ref "R30") (pin "1") (pinfunction "1_1") (pintype "passive"))
    )
    (net (code "87") (name "Net-(Q15-PadD)") (class "Default")
      (node (ref "Q15") (pin "D") (pinfunction "D_D") (pintype "passive"))
      (node (ref "R31") (pin "1") (pinfunction "1_1") (pintype "passive"))
    )
    (net (code "88") (name "Net-(Q16-PadD)") (class "Default")
      (node (ref "Q16") (pin "D") (pinfunction "D_D") (pintype "passive"))
      (node (ref "R32") (pin "1") (pinfunction "1_1") (pintype "passive"))
    )
    (net (code "89") (name "Net-(Q17-PadD)") (class "Default")
      (node (ref "Q17") (pin "D") (pinfunction "D_D") (pintype "passive"))
      (node (ref "R56") (pin "1") (pinfunction "1_1") (pintype "passive"))
    )
    (net (code "90") (name "Net-(R34-Pad2)") (class "Default")
      (node (ref "R34") (pin "2") (pinfunction "2_2") (pintype "passive"))
      (node (ref "R35") (pin "2") (pinfunction "2_2") (pintype "passive"))
      (node (ref "R36") (pin "2") (pinfunction "2_2") (pintype "passive"))
      (node (ref "R37") (pin "2") (pinfunction "2_2") (pintype "passive"))
      (node (ref "R38") (pin "2") (pinfunction "2_2") (pintype "passive"))
      (node (ref "R39") (pin "2") (pinfunction "2_2") (pintype "passive"))
      (node (ref "R40") (pin "2") (pinfunction "2_2") (pintype "passive"))
      (node (ref "R41") (pin "2") (pinfunction "2_2") (pintype "passive"))
      (node (ref "R42") (pin "2") (pinfunction "2_2") (pintype "passive"))
      (node (ref "R43") (pin "2") (pinfunction "2_2") (pintype "passive"))
      (node (ref "R44") (pin "2") (pinfunction "2_2") (pintype "passive"))
      (node (ref "R45") (pin "2") (pinfunction "2_2") (pintype "passive"))
      (node (ref "R46") (pin "2") (pinfunction "2_2") (pintype "passive"))
      (node (ref "R47") (pin "2") (pinfunction "2_2") (pintype "passive"))
      (node (ref "R48") (pin "2") (pinfunction "2_2") (pintype "passive"))
      (node (ref "R49") (pin "2") (pinfunction "2_2") (pintype "passive"))
      (node (ref "R50") (pin "2") (pinfunction "2_2") (pintype "passive"))
      (node (ref "R51") (pin "2") (pinfunction "2_2") (pintype "passive"))
      (node (ref "R52") (pin "2") (pinfunction "2_2") (pintype "passive"))
      (node (ref "R53") (pin "2") (pinfunction "2_2") (pintype "passive"))
      (node (ref "R60") (pin "2") (pinfunction "2_2") (pintype "passive"))
    )
    (net (code "91") (name "Net-(R56-Pad2)") (class "Default")
      (node (ref "R56") (pin "2") (pinfunction "2_2") (pintype "passive"))
      (node (ref "SG1") (pin "1") (pinfunction "1_1") (pintype "passive"))
    )
    (net (code "92") (name "unconnected-(IC2A-~{QH}-Pad7)") (class "Default")
      (node (ref "IC2") (pin "7") (pinfunction "~{QH}_7") (pintype "output"))
    )
    (net (code "93") (name "unconnected-(IC3A-~{QH}-Pad7)") (class "Default")
      (node (ref "IC3") (pin "7") (pinfunction "~{QH}_7") (pintype "output"))
    )
    (net (code "94") (name "unconnected-(IC5A-QH*-Pad9)") (class "Default")
      (node (ref "IC5") (pin "9") (pinfunction "QH*_9") (pintype "tri_state"))
    )
    (net (code "95") (name "unconnected-(IC7D-O-Pad8)") (class "Default")
      (node (ref "IC7") (pin "8") (pinfunction "O_8") (pintype "output"))
    )
    (net (code "96") (name "unconnected-(IC7E-O-Pad10)") (class "Default")
      (node (ref "IC7") (pin "10") (pinfunction "O_10") (pintype "output"))
    )
    (net (code "97") (name "unconnected-(IC7F-O-Pad12)") (class "Default")
      (node (ref "IC7") (pin "12") (pinfunction "O_12") (pintype "output"))
    )
    (net (code "98") (name "unconnected-(J8H-S-Pad16)") (class "Default")
      (node (ref "J8") (pin "16") (pinfunction "S_16") (pintype "passive"))
    )
    (net (code "99") (name "unconnected-(Q2-PadS)") (class "Default")
      (node (ref "Q2") (pin "S") (pinfunction "S_S") (pintype "passive"))
    )
    (net (code "100") (name "unconnected-(Q3-PadS)") (class "Default")
      (node (ref "Q3") (pin "S") (pinfunction "S_S") (pintype "passive"))
    )
    (net (code "101") (name "unconnected-(Q4-PadS)") (class "Default")
      (node (ref "Q4") (pin "S") (pinfunction "S_S") (pintype "passive"))
    )
    (net (code "102") (name "unconnected-(Q5-PadS)") (class "Default")
      (node (ref "Q5") (pin "S") (pinfunction "S_S") (pintype "passive"))
    )
    (net (code "103") (name "unconnected-(Q6-PadS)") (class "Default")
      (node (ref "Q6") (pin "S") (pinfunction "S_S") (pintype "passive"))
    )
    (net (code "104") (name "unconnected-(Q7-PadS)") (class "Default")
      (node (ref "Q7") (pin "S") (pinfunction "S_S") (pintype "passive"))
    )
    (net (code "105") (name "unconnected-(Q8-PadS)") (class "Default")
      (node (ref "Q8") (pin "S") (pinfunction "S_S") (pintype "passive"))
    )
  )
)
